# jr_pro_reverb.net
KiCad netlist of a schematic drawn in EAGLE
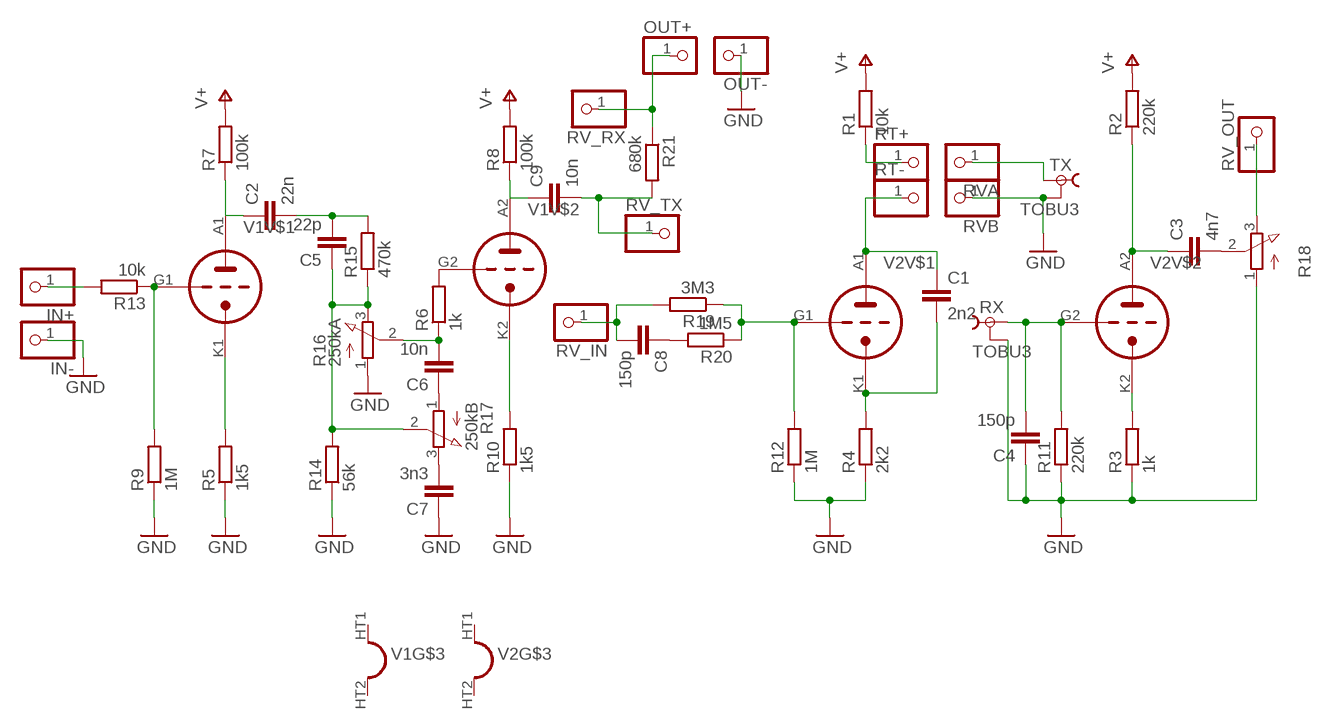
[diagram p0: schematic, sheet 1]

(export (version "E")
  (design (tool "Eeschema 10.0.6"))
  (components
    (comp (ref "C1")
      (value "2n2")
      (footprint "eagle-import:C050-030X075")
      (libsource (lib "eagle-import") (part "C-EU050-030X075"))
    )
    (comp (ref "C2")
      (value "22n")
      (footprint "eagle-import:C050-045X075")
      (libsource (lib "eagle-import") (part "C-EU050-045X075"))
    )
    (comp (ref "C3")
      (value "4n7")
      (footprint "eagle-import:C050-045X075")
      (libsource (lib "eagle-import") (part "C-EU050-045X075"))
    )
    (comp (ref "C4")
      (value "150p")
      (footprint "eagle-import:C050-030X075")
      (libsource (lib "eagle-import") (part "C-EU050-030X075"))
    )
    (comp (ref "C5")
      (value "22p")
      (footprint "eagle-import:C050-030X075")
      (libsource (lib "eagle-import") (part "C-EU050-030X075"))
    )
    (comp (ref "C6")
      (value "10n")
      (footprint "eagle-import:C050-045X075")
      (libsource (lib "eagle-import") (part "C-EU050-045X075"))
    )
    (comp (ref "C7")
      (value "3n3")
      (footprint "eagle-import:C050-045X075")
      (libsource (lib "eagle-import") (part "C-EU050-045X075"))
    )
    (comp (ref "C8")
      (value "150p")
      (footprint "eagle-import:C050-030X075")
      (libsource (lib "eagle-import") (part "C-EU050-030X075"))
    )
    (comp (ref "C9")
      (value "10n")
      (footprint "eagle-import:C050-045X075")
      (libsource (lib "eagle-import") (part "C-EU050-045X075"))
    )
    (comp (ref "IN+")
      (value "PINHD-1X1")
      (footprint "eagle-import:1X01")
      (libsource (lib "eagle-import") (part "PINHD-1X1"))
    )
    (comp (ref "IN-")
      (value "PINHD-1X1")
      (footprint "eagle-import:1X01")
      (libsource (lib "eagle-import") (part "PINHD-1X1"))
    )
    (comp (ref "OUT+")
      (value "PINHD-1X1")
      (footprint "eagle-import:1X01")
      (libsource (lib "eagle-import") (part "PINHD-1X1"))
    )
    (comp (ref "OUT-")
      (value "PINHD-1X1")
      (footprint "eagle-import:1X01")
      (libsource (lib "eagle-import") (part "PINHD-1X1"))
    )
    (comp (ref "R1")
      (value "10k")
      (footprint "eagle-import:0207_7")
      (libsource (lib "eagle-import") (part "R-EU_0207/7"))
    )
    (comp (ref "R2")
      (value "220k")
      (footprint "eagle-import:0207_7")
      (libsource (lib "eagle-import") (part "R-EU_0207/7"))
    )
    (comp (ref "R3")
      (value "1k")
      (footprint "eagle-import:0207_7")
      (libsource (lib "eagle-import") (part "R-EU_0207/7"))
    )
    (comp (ref "R4")
      (value "2k2")
      (footprint "eagle-import:0207_7")
      (libsource (lib "eagle-import") (part "R-EU_0207/7"))
    )
    (comp (ref "R5")
      (value "1k5")
      (footprint "eagle-import:0207_7")
      (libsource (lib "eagle-import") (part "R-EU_0207/7"))
    )
    (comp (ref "R6")
      (value "1k")
      (footprint "eagle-import:0207_7")
      (libsource (lib "eagle-import") (part "R-EU_0207/7"))
    )
    (comp (ref "R7")
      (value "100k")
      (footprint "eagle-import:0207_7")
      (libsource (lib "eagle-import") (part "R-EU_0207/7"))
    )
    (comp (ref "R8")
      (value "100k")
      (footprint "eagle-import:0207_7")
      (libsource (lib "eagle-import") (part "R-EU_0207/7"))
    )
    (comp (ref "R9")
      (value "1M")
      (footprint "eagle-import:0207_7")
      (libsource (lib "eagle-import") (part "R-EU_0207/7"))
    )
    (comp (ref "R10")
      (value "1k5")
      (footprint "eagle-import:0207_7")
      (libsource (lib "eagle-import") (part "R-EU_0207/7"))
    )
    (comp (ref "R11")
      (value "220k")
      (footprint "eagle-import:0207_7")
      (libsource (lib "eagle-import") (part "R-EU_0207/7"))
    )
    (comp (ref "R12")
      (value "1M")
      (footprint "eagle-import:0207_7")
      (libsource (lib "eagle-import") (part "R-EU_0207/7"))
    )
    (comp (ref "R13")
      (value "10k")
      (footprint "eagle-import:0207_7")
      (libsource (lib "eagle-import") (part "R-EU_0207/7"))
    )
    (comp (ref "R14")
      (value "56k")
      (footprint "eagle-import:0207_7")
      (libsource (lib "eagle-import") (part "R-EU_0207/7"))
    )
    (comp (ref "R15")
      (value "470k")
      (footprint "eagle-import:0207_7")
      (libsource (lib "eagle-import") (part "R-EU_0207/7"))
    )
    (comp (ref "R16")
      (value "250kA")
      (footprint "eagle-import:3RP_1610N")
      (libsource (lib "eagle-import") (part "3RP/1610N"))
    )
    (comp (ref "R17")
      (value "250kB")
      (footprint "eagle-import:3RP_1610N")
      (libsource (lib "eagle-import") (part "3RP/1610N"))
    )
    (comp (ref "R18")
      (value "3RP/1610N")
      (footprint "eagle-import:3RP_1610N")
      (libsource (lib "eagle-import") (part "3RP/1610N"))
    )
    (comp (ref "R19")
      (value "3M3")
      (footprint "eagle-import:0207_7")
      (libsource (lib "eagle-import") (part "R-EU_0207/7"))
    )
    (comp (ref "R20")
      (value "1M5")
      (footprint "eagle-import:0207_7")
      (libsource (lib "eagle-import") (part "R-EU_0207/7"))
    )
    (comp (ref "R21")
      (value "680k")
      (footprint "eagle-import:0207_7")
      (libsource (lib "eagle-import") (part "R-EU_0207/7"))
    )
    (comp (ref "RT+")
      (value "PINHD-1X1")
      (footprint "eagle-import:1X01")
      (libsource (lib "eagle-import") (part "PINHD-1X1"))
    )
    (comp (ref "RT-")
      (value "PINHD-1X1")
      (footprint "eagle-import:1X01")
      (libsource (lib "eagle-import") (part "PINHD-1X1"))
    )
    (comp (ref "RVA")
      (value "PINHD-1X1")
      (footprint "eagle-import:1X01")
      (libsource (lib "eagle-import") (part "PINHD-1X1"))
    )
    (comp (ref "RVB")
      (value "PINHD-1X1")
      (footprint "eagle-import:1X01")
      (libsource (lib "eagle-import") (part "PINHD-1X1"))
    )
    (comp (ref "RV_IN")
      (value "PINHD-1X1")
      (footprint "eagle-import:1X01")
      (libsource (lib "eagle-import") (part "PINHD-1X1"))
    )
    (comp (ref "RV_OUT")
      (value "PINHD-1X1")
      (footprint "eagle-import:1X01")
      (libsource (lib "eagle-import") (part "PINHD-1X1"))
    )
    (comp (ref "RV_RX")
      (value "PINHD-1X1")
      (footprint "eagle-import:1X01")
      (libsource (lib "eagle-import") (part "PINHD-1X1"))
    )
    (comp (ref "RV_TX")
      (value "PINHD-1X1")
      (footprint "eagle-import:1X01")
      (libsource (lib "eagle-import") (part "PINHD-1X1"))
    )
    (comp (ref "RX")
      (value "TOBU3")
      (footprint "eagle-import:TOBU3")
      (fields (field (name "MF") "FARNELL") (field (name "MPN") "TOBU 3"))
      (libsource (lib "eagle-import") (part "TOBU3"))
    )
    (comp (ref "TX")
      (value "TOBU3")
      (footprint "eagle-import:TOBU3")
      (fields (field (name "MF") "FARNELL") (field (name "MPN") "TOBU 3"))
      (libsource (lib "eagle-import") (part "TOBU3"))
    )
    (comp (ref "V1")
      (value "6NXX-PIT")
      (footprint "eagle-import:6NXX-PIT")
      (libsource (lib "eagle-import") (part "6NXX-PIT"))
    )
    (comp (ref "V2")
      (value "6NXX-PIT")
      (footprint "eagle-import:6NXX-PIT")
      (libsource (lib "eagle-import") (part "6NXX-PIT"))
    )
  )
  (nets
    (net (code "1") (name "GND") (class "Default")
      (node (ref "C4") (pin "1") (pinfunction "1_1") (pintype "passive"))
      (node (ref "C7") (pin "1") (pinfunction "1_1") (pintype "passive"))
      (node (ref "IN-") (pin "1") (pinfunction "1_1") (pintype "passive"))
      (node (ref "OUT-") (pin "1") (pinfunction "1_1") (pintype "passive"))
      (node (ref "R10") (pin "1") (pinfunction "1_1") (pintype "passive"))
      (node (ref "R11") (pin "1") (pinfunction "1_1") (pintype "passive"))
      (node (ref "R12") (pin "1") (pinfunction "1_1") (pintype "passive"))
      (node (ref "R14") (pin "1") (pinfunction "1_1") (pintype "passive"))
      (node (ref "R16") (pin "1") (pinfunction "A_1") (pintype "passive"))
      (node (ref "R18") (pin "1") (pinfunction "A_1") (pintype "passive"))
      (node (ref "R3") (pin "1") (pinfunction "1_1") (pintype "passive"))
      (node (ref "R4") (pin "1") (pinfunction "1_1") (pintype "passive"))
      (node (ref "R5") (pin "1") (pinfunction "1_1") (pintype "passive"))
      (node (ref "R9") (pin "1") (pinfunction "1_1") (pintype "passive"))
      (node (ref "RVB") (pin "1") (pinfunction "1_1") (pintype "passive"))
      (node (ref "RX") (pin "2") (pinfunction "2_2") (pintype "passive"))
      (node (ref "RX") (pin "2@1") (pinfunction "2_2@1") (pintype "passive"))
      (node (ref "RX") (pin "2@2") (pinfunction "2_2@2") (pintype "passive"))
      (node (ref "TX") (pin "2") (pinfunction "2_2") (pintype "passive"))
      (node (ref "TX") (pin "2@1") (pinfunction "2_2@1") (pintype "passive"))
      (node (ref "TX") (pin "2@2") (pinfunction "2_2@2") (pintype "passive"))
    )
    (net (code "2") (name "Net-(C2-Pad2)") (class "Default")
      (node (ref "C2") (pin "2") (pinfunction "2_2") (pintype "passive"))
      (node (ref "C5") (pin "2") (pinfunction "2_2") (pintype "passive"))
      (node (ref "R15") (pin "2") (pinfunction "2_2") (pintype "passive"))
    )
    (net (code "3") (name "Net-(C8-Pad1)") (class "Default")
      (node (ref "C8") (pin "1") (pinfunction "1_1") (pintype "passive"))
      (node (ref "R20") (pin "2") (pinfunction "2_2") (pintype "passive"))
    )
    (net (code "4") (name "Net-(C8-Pad2)") (class "Default")
      (node (ref "C8") (pin "2") (pinfunction "2_2") (pintype "passive"))
      (node (ref "R19") (pin "2") (pinfunction "2_2") (pintype "passive"))
      (node (ref "RV_IN") (pin "1") (pinfunction "1_1") (pintype "passive"))
    )
    (net (code "5") (name "Net-(C9-Pad2)") (class "Default")
      (node (ref "C9") (pin "2") (pinfunction "2_2") (pintype "passive"))
      (node (ref "R21") (pin "2") (pinfunction "2_2") (pintype "passive"))
      (node (ref "RV_TX") (pin "1") (pinfunction "1_1") (pintype "passive"))
    )
    (net (code "6") (name "Net-(IN+-Pad1)") (class "Default")
      (node (ref "IN+") (pin "1") (pinfunction "1_1") (pintype "passive"))
      (node (ref "R13") (pin "2") (pinfunction "2_2") (pintype "passive"))
    )
    (net (code "7") (name "Net-(OUT+-Pad1)") (class "Default")
      (node (ref "OUT+") (pin "1") (pinfunction "1_1") (pintype "passive"))
      (node (ref "R21") (pin "1") (pinfunction "1_1") (pintype "passive"))
      (node (ref "RV_RX") (pin "1") (pinfunction "1_1") (pintype "passive"))
    )
    (net (code "8") (name "Net-(R1-Pad1)") (class "Default")
      (node (ref "R1") (pin "1") (pinfunction "1_1") (pintype "passive"))
      (node (ref "RT+") (pin "1") (pinfunction "1_1") (pintype "passive"))
    )
    (net (code "9") (name "Net-(R16-E)") (class "Default")
      (node (ref "C5") (pin "1") (pinfunction "1_1") (pintype "passive"))
      (node (ref "R14") (pin "2") (pinfunction "2_2") (pintype "passive"))
      (node (ref "R15") (pin "1") (pinfunction "1_1") (pintype "passive"))
      (node (ref "R16") (pin "3") (pinfunction "E_3") (pintype "passive"))
      (node (ref "R17") (pin "2") (pinfunction "S_2") (pintype "passive"))
    )
    (net (code "10") (name "Net-(R16-S)") (class "Default")
      (node (ref "C6") (pin "2") (pinfunction "2_2") (pintype "passive"))
      (node (ref "R16") (pin "2") (pinfunction "S_2") (pintype "passive"))
      (node (ref "R6") (pin "1") (pinfunction "1_1") (pintype "passive"))
    )
    (net (code "11") (name "Net-(R17-A)") (class "Default")
      (node (ref "C6") (pin "1") (pinfunction "1_1") (pintype "passive"))
      (node (ref "R17") (pin "1") (pinfunction "A_1") (pintype "passive"))
    )
    (net (code "12") (name "Net-(R17-E)") (class "Default")
      (node (ref "C7") (pin "2") (pinfunction "2_2") (pintype "passive"))
      (node (ref "R17") (pin "3") (pinfunction "E_3") (pintype "passive"))
    )
    (net (code "13") (name "Net-(R18-E)") (class "Default")
      (node (ref "R18") (pin "3") (pinfunction "E_3") (pintype "passive"))
      (node (ref "RV_OUT") (pin "1") (pinfunction "1_1") (pintype "passive"))
    )
    (net (code "14") (name "Net-(R18-S)") (class "Default")
      (node (ref "C3") (pin "2") (pinfunction "2_2") (pintype "passive"))
      (node (ref "R18") (pin "2") (pinfunction "S_2") (pintype "passive"))
    )
    (net (code "15") (name "Net-(RVA-Pad1)") (class "Default")
      (node (ref "RVA") (pin "1") (pinfunction "1_1") (pintype "passive"))
      (node (ref "TX") (pin "1") (pinfunction "1_1") (pintype "passive"))
    )
    (net (code "16") (name "Net-(V1B-TA)") (class "Default")
      (node (ref "C2") (pin "1") (pinfunction "1_1") (pintype "passive"))
      (node (ref "R7") (pin "1") (pinfunction "1_1") (pintype "passive"))
      (node (ref "V1") (pin "A1") (pinfunction "TA_A1") (pintype "passive"))
    )
    (net (code "17") (name "Net-(V1B-TG)") (class "Default")
      (node (ref "R13") (pin "1") (pinfunction "1_1") (pintype "passive"))
      (node (ref "R9") (pin "2") (pinfunction "2_2") (pintype "passive"))
      (node (ref "V1") (pin "G1") (pinfunction "TG_G1") (pintype "passive"))
    )
    (net (code "18") (name "Net-(V1B-TK)") (class "Default")
      (node (ref "R5") (pin "2") (pinfunction "2_2") (pintype "passive"))
      (node (ref "V1") (pin "K1") (pinfunction "TK_K1") (pintype "passive"))
    )
    (net (code "19") (name "Net-(V1C-TA)") (class "Default")
      (node (ref "C9") (pin "1") (pinfunction "1_1") (pintype "passive"))
      (node (ref "R8") (pin "1") (pinfunction "1_1") (pintype "passive"))
      (node (ref "V1") (pin "A2") (pinfunction "TA_A2") (pintype "passive"))
    )
    (net (code "20") (name "Net-(V1C-TG)") (class "Default")
      (node (ref "R6") (pin "2") (pinfunction "2_2") (pintype "passive"))
      (node (ref "V1") (pin "G2") (pinfunction "TG_G2") (pintype "passive"))
    )
    (net (code "21") (name "Net-(V1C-TK)") (class "Default")
      (node (ref "R10") (pin "2") (pinfunction "2_2") (pintype "passive"))
      (node (ref "V1") (pin "K2") (pinfunction "TK_K2") (pintype "passive"))
    )
    (net (code "22") (name "Net-(V2B-TA)") (class "Default")
      (node (ref "C1") (pin "1") (pinfunction "1_1") (pintype "passive"))
      (node (ref "RT-") (pin "1") (pinfunction "1_1") (pintype "passive"))
      (node (ref "V2") (pin "A1") (pinfunction "TA_A1") (pintype "passive"))
    )
    (net (code "23") (name "Net-(V2B-TG)") (class "Default")
      (node (ref "R12") (pin "2") (pinfunction "2_2") (pintype "passive"))
      (node (ref "R19") (pin "1") (pinfunction "1_1") (pintype "passive"))
      (node (ref "R20") (pin "1") (pinfunction "1_1") (pintype "passive"))
      (node (ref "V2") (pin "G1") (pinfunction "TG_G1") (pintype "passive"))
    )
    (net (code "24") (name "Net-(V2B-TK)") (class "Default")
      (node (ref "C1") (pin "2") (pinfunction "2_2") (pintype "passive"))
      (node (ref "R4") (pin "2") (pinfunction "2_2") (pintype "passive"))
      (node (ref "V2") (pin "K1") (pinfunction "TK_K1") (pintype "passive"))
    )
    (net (code "25") (name "Net-(V2C-TA)") (class "Default")
      (node (ref "C3") (pin "1") (pinfunction "1_1") (pintype "passive"))
      (node (ref "R2") (pin "1") (pinfunction "1_1") (pintype "passive"))
      (node (ref "V2") (pin "A2") (pinfunction "TA_A2") (pintype "passive"))
    )
    (net (code "26") (name "Net-(V2C-TG)") (class "Default")
      (node (ref "C4") (pin "2") (pinfunction "2_2") (pintype "passive"))
      (node (ref "R11") (pin "2") (pinfunction "2_2") (pintype "passive"))
      (node (ref "RX") (pin "1") (pinfunction "1_1") (pintype "passive"))
      (node (ref "V2") (pin "G2") (pinfunction "TG_G2") (pintype "passive"))
    )
    (net (code "27") (name "Net-(V2C-TK)") (class "Default")
      (node (ref "R3") (pin "2") (pinfunction "2_2") (pintype "passive"))
      (node (ref "V2") (pin "K2") (pinfunction "TK_K2") (pintype "passive"))
    )
    (net (code "28") (name "V+") (class "Default")
      (node (ref "R1") (pin "2") (pinfunction "2_2") (pintype "passive"))
      (node (ref "R2") (pin "2") (pinfunction "2_2") (pintype "passive"))
      (node (ref "R7") (pin "2") (pinfunction "2_2") (pintype "passive"))
      (node (ref "R8") (pin "2") (pinfunction "2_2") (pintype "passive"))
    )
    (net (code "29") (name "unconnected-(V1A-H1-PadHT1)") (class "Default")
      (node (ref "V1") (pin "HT1") (pinfunction "H1_HT1") (pintype "passive"))
    )
    (net (code "30") (name "unconnected-(V1A-H2-PadHT2)") (class "Default")
      (node (ref "V1") (pin "HT2") (pinfunction "H2_HT2") (pintype "passive"))
    )
    (net (code "31") (name "unconnected-(V2A-H1-PadHT1)") (class "Default")
      (node (ref "V2") (pin "HT1") (pinfunction "H1_HT1") (pintype "passive"))
    )
    (net (code "32") (name "unconnected-(V2A-H2-PadHT2)") (class "Default")
      (node (ref "V2") (pin "HT2") (pinfunction "H2_HT2") (pintype "passive"))
    )
  )
)
